# x0_logic_v0001.net
KiCad netlist of a schematic drawn in EAGLE
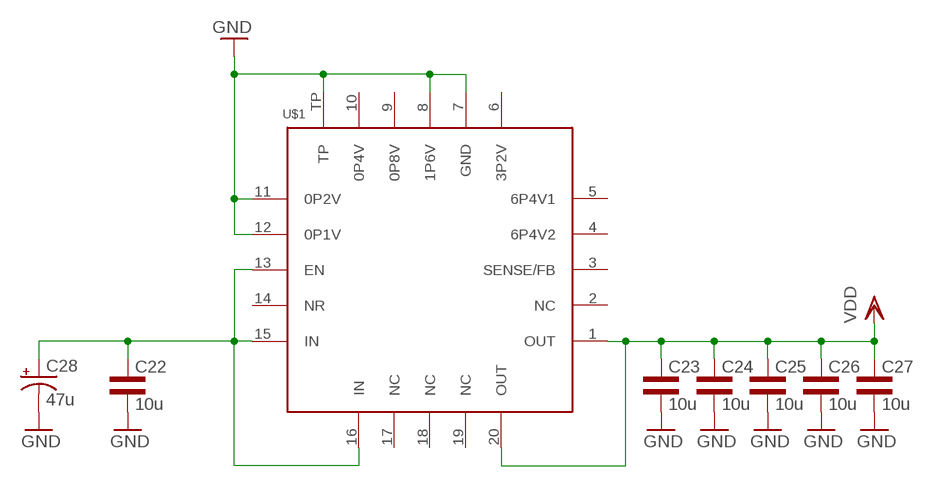
[diagram p0: schematic, sheet 1]
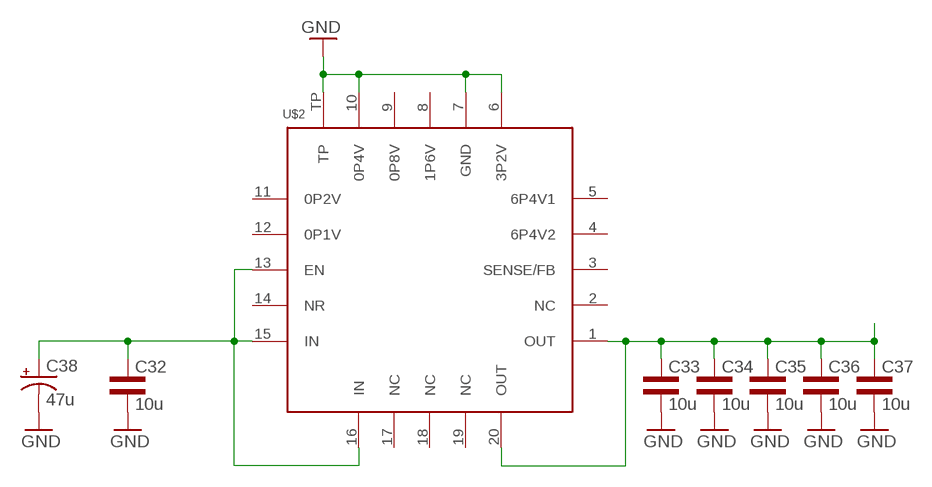
[diagram p1: schematic, sheet 2]
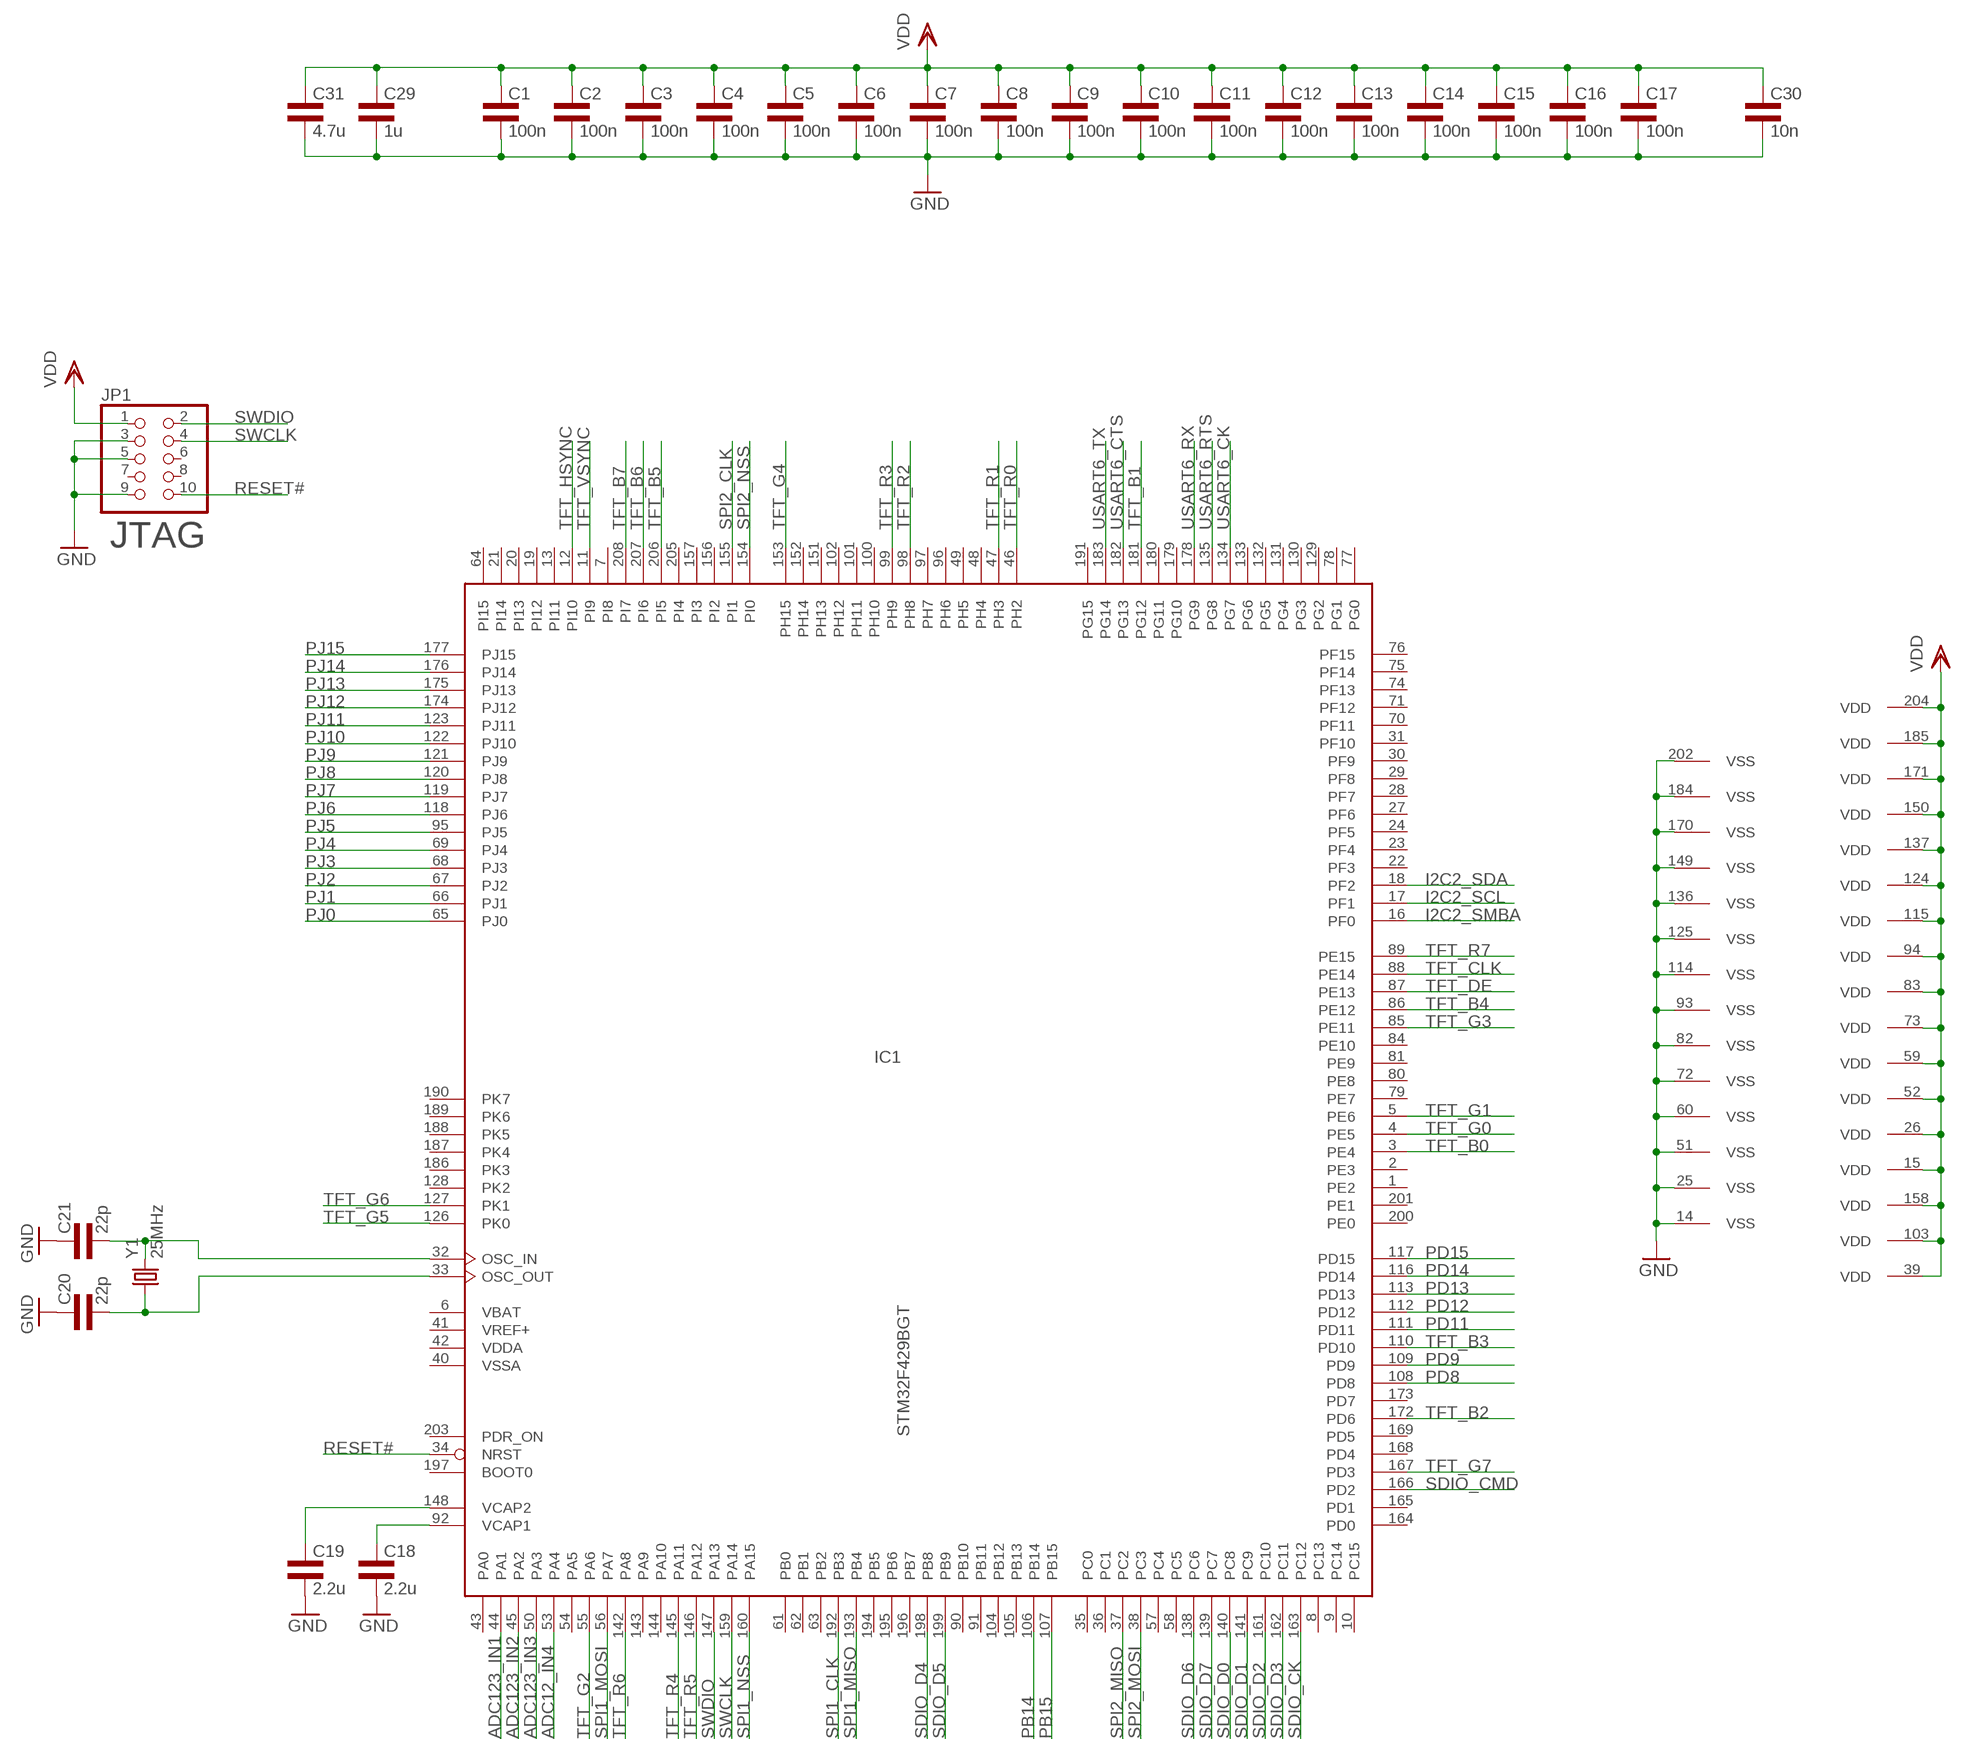
[diagram p2: schematic, sheet 3]
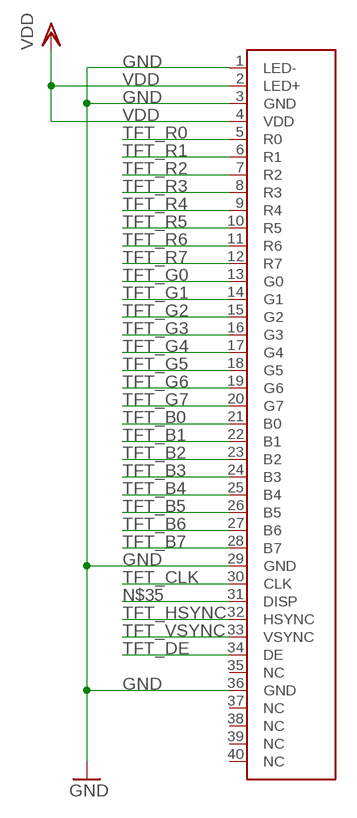
[diagram p3: schematic, sheet 4]
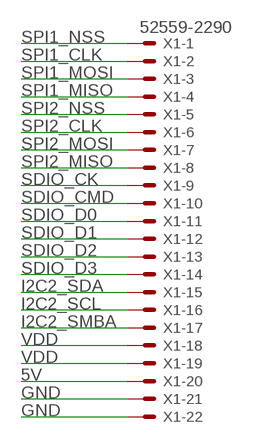
[diagram p4: schematic, sheet 5]
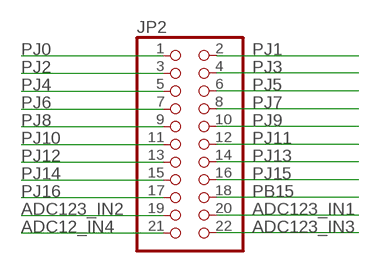
[diagram p5: schematic, sheet 6]
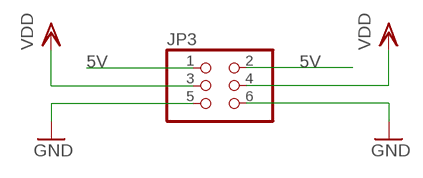
[diagram p6: schematic, sheet 7]

(export (version "E")
  (design (tool "Eeschema 10.0.6"))
  (components
    (comp (ref "C32")
      (value "10u")
      (footprint "eagle-import:1206L3")
      (libsource (lib "eagle-import") (part "CAP1206L3"))
    )
    (comp (ref "C33")
      (value "10u")
      (footprint "eagle-import:1206L3")
      (libsource (lib "eagle-import") (part "CAP1206L3"))
    )
    (comp (ref "C34")
      (value "10u")
      (footprint "eagle-import:1206L3")
      (libsource (lib "eagle-import") (part "CAP1206L3"))
    )
    (comp (ref "C35")
      (value "10u")
      (footprint "eagle-import:1206L3")
      (libsource (lib "eagle-import") (part "CAP1206L3"))
    )
    (comp (ref "C36")
      (value "10u")
      (footprint "eagle-import:1206L3")
      (libsource (lib "eagle-import") (part "CAP1206L3"))
    )
    (comp (ref "C37")
      (value "10u")
      (footprint "eagle-import:1206L3")
      (libsource (lib "eagle-import") (part "CAP1206L3"))
    )
    (comp (ref "C38")
      (value "47u")
      (footprint "eagle-import:CT7343")
      (libsource (lib "eagle-import") (part "CPOL-USCT7343"))
    )
    (comp (ref "U$2")
      (value "POWER-SUPPLY_POS_V1_TI_LDO_TPS7A4700")
      (footprint "eagle-import:POWER-SUPPLY_POS_V1_TI_LDO_VQFN-20")
      (libsource (lib "eagle-import") (part "POWER-SUPPLY_POS_V1_TI_LDO_TPS7A4700"))
    )
    (comp (ref "X1")
      (value "52559-2290")
      (footprint "eagle-import:52559-2290")
      (libsource (lib "eagle-import") (part "52559-2290"))
    )
    (comp (ref "JP3")
      (value "PINHD-2X3")
      (footprint "eagle-import:2X03")
      (libsource (lib "eagle-import") (part "PINHD-2X3"))
    )
    (comp (ref "CON1")
      (value "NH-4.3")
      (footprint "eagle-import:FPC-40")
      (libsource (lib "eagle-import") (part "NH-4.3"))
    )
    (comp (ref "C22")
      (value "10u")
      (footprint "eagle-import:1206L3")
      (libsource (lib "eagle-import") (part "CAP1206L3"))
    )
    (comp (ref "C23")
      (value "10u")
      (footprint "eagle-import:1206L3")
      (libsource (lib "eagle-import") (part "CAP1206L3"))
    )
    (comp (ref "C24")
      (value "10u")
      (footprint "eagle-import:1206L3")
      (libsource (lib "eagle-import") (part "CAP1206L3"))
    )
    (comp (ref "C25")
      (value "10u")
      (footprint "eagle-import:1206L3")
      (libsource (lib "eagle-import") (part "CAP1206L3"))
    )
    (comp (ref "C26")
      (value "10u")
      (footprint "eagle-import:1206L3")
      (libsource (lib "eagle-import") (part "CAP1206L3"))
    )
    (comp (ref "C27")
      (value "10u")
      (footprint "eagle-import:1206L3")
      (libsource (lib "eagle-import") (part "CAP1206L3"))
    )
    (comp (ref "C28")
      (value "47u")
      (footprint "eagle-import:CT7343")
      (libsource (lib "eagle-import") (part "CPOL-USCT7343"))
    )
    (comp (ref "U$1")
      (value "POWER-SUPPLY_POS_V1_TI_LDO_TPS7A4700")
      (footprint "eagle-import:POWER-SUPPLY_POS_V1_TI_LDO_VQFN-20")
      (libsource (lib "eagle-import") (part "POWER-SUPPLY_POS_V1_TI_LDO_TPS7A4700"))
    )
    (comp (ref "C1")
      (value "100n")
      (footprint "eagle-import:0402L3")
      (libsource (lib "eagle-import") (part "CAP0402L3"))
    )
    (comp (ref "C2")
      (value "100n")
      (footprint "eagle-import:0402L3")
      (libsource (lib "eagle-import") (part "CAP0402L3"))
    )
    (comp (ref "C3")
      (value "100n")
      (footprint "eagle-import:0402L3")
      (libsource (lib "eagle-import") (part "CAP0402L3"))
    )
    (comp (ref "C4")
      (value "100n")
      (footprint "eagle-import:0402L3")
      (libsource (lib "eagle-import") (part "CAP0402L3"))
    )
    (comp (ref "C5")
      (value "100n")
      (footprint "eagle-import:0402L3")
      (libsource (lib "eagle-import") (part "CAP0402L3"))
    )
    (comp (ref "C6")
      (value "100n")
      (footprint "eagle-import:0402L3")
      (libsource (lib "eagle-import") (part "CAP0402L3"))
    )
    (comp (ref "C7")
      (value "100n")
      (footprint "eagle-import:0402L3")
      (libsource (lib "eagle-import") (part "CAP0402L3"))
    )
    (comp (ref "C8")
      (value "100n")
      (footprint "eagle-import:0402L3")
      (libsource (lib "eagle-import") (part "CAP0402L3"))
    )
    (comp (ref "C9")
      (value "100n")
      (footprint "eagle-import:0402L3")
      (libsource (lib "eagle-import") (part "CAP0402L3"))
    )
    (comp (ref "C10")
      (value "100n")
      (footprint "eagle-import:0402L3")
      (libsource (lib "eagle-import") (part "CAP0402L3"))
    )
    (comp (ref "C11")
      (value "100n")
      (footprint "eagle-import:0402L3")
      (libsource (lib "eagle-import") (part "CAP0402L3"))
    )
    (comp (ref "C12")
      (value "100n")
      (footprint "eagle-import:0402L3")
      (libsource (lib "eagle-import") (part "CAP0402L3"))
    )
    (comp (ref "C13")
      (value "100n")
      (footprint "eagle-import:0402L3")
      (libsource (lib "eagle-import") (part "CAP0402L3"))
    )
    (comp (ref "C14")
      (value "100n")
      (footprint "eagle-import:0402L3")
      (libsource (lib "eagle-import") (part "CAP0402L3"))
    )
    (comp (ref "C15")
      (value "100n")
      (footprint "eagle-import:0402L3")
      (libsource (lib "eagle-import") (part "CAP0402L3"))
    )
    (comp (ref "C16")
      (value "100n")
      (footprint "eagle-import:0402L3")
      (libsource (lib "eagle-import") (part "CAP0402L3"))
    )
    (comp (ref "C17")
      (value "100n")
      (footprint "eagle-import:0402L3")
      (libsource (lib "eagle-import") (part "CAP0402L3"))
    )
    (comp (ref "C18")
      (value "2.2u")
      (footprint "eagle-import:0603L3")
      (libsource (lib "eagle-import") (part "CAP0603L3"))
    )
    (comp (ref "C19")
      (value "2.2u")
      (footprint "eagle-import:0603L3")
      (libsource (lib "eagle-import") (part "CAP0603L3"))
    )
    (comp (ref "C20")
      (value "22p")
      (footprint "eagle-import:0402L3")
      (libsource (lib "eagle-import") (part "CAP0402L3"))
    )
    (comp (ref "C21")
      (value "22p")
      (footprint "eagle-import:0402L3")
      (libsource (lib "eagle-import") (part "CAP0402L3"))
    )
    (comp (ref "C29")
      (value "1u")
      (footprint "eagle-import:0805L3")
      (libsource (lib "eagle-import") (part "CAP0805L3"))
    )
    (comp (ref "C30")
      (value "10n")
      (footprint "eagle-import:0603L3")
      (libsource (lib "eagle-import") (part "CAP0603L3"))
    )
    (comp (ref "C31")
      (value "4.7u")
      (footprint "eagle-import:0805L3")
      (libsource (lib "eagle-import") (part "CAP0805L3"))
    )
    (comp (ref "IC1")
      (value "STM32F429BGT")
      (footprint "eagle-import:LQFP208")
      (libsource (lib "eagle-import") (part "STM32F429BTG"))
    )
    (comp (ref "JP1")
      (value "PINHD-2X5")
      (footprint "eagle-import:2X05")
      (libsource (lib "eagle-import") (part "PINHD-2X5"))
    )
    (comp (ref "Y1")
      (value "25MHz")
      (footprint "eagle-import:HC49US")
      (libsource (lib "eagle-import") (part "CRYSTALHC49US"))
    )
    (comp (ref "JP2")
      (value "PINHD-2X11")
      (footprint "eagle-import:2X11")
      (libsource (lib "eagle-import") (part "PINHD-2X11"))
    )
  )
  (nets
    (net (code "1") (name "5V") (class "Default")
      (node (ref "C33") (pin "1") (pinfunction "1_1") (pintype "bidirectional"))
      (node (ref "C34") (pin "1") (pinfunction "1_1") (pintype "bidirectional"))
      (node (ref "C35") (pin "1") (pinfunction "1_1") (pintype "bidirectional"))
      (node (ref "C36") (pin "1") (pinfunction "1_1") (pintype "bidirectional"))
      (node (ref "C37") (pin "1") (pinfunction "1_1") (pintype "bidirectional"))
      (node (ref "JP3") (pin "1") (pinfunction "1_1") (pintype "passive"))
      (node (ref "JP3") (pin "2") (pinfunction "2_2") (pintype "passive"))
      (node (ref "U$2") (pin "1") (pinfunction "OUT_1") (pintype "bidirectional"))
      (node (ref "U$2") (pin "20") (pinfunction "OUT_20") (pintype "bidirectional"))
      (node (ref "X1") (pin "20") (pinfunction "S_20") (pintype "passive"))
    )
    (net (code "2") (name "ADC12_IN4") (class "Default")
      (node (ref "IC1") (pin "53") (pinfunction "PA4_53") (pintype "bidirectional"))
      (node (ref "JP2") (pin "21") (pinfunction "21_21") (pintype "passive"))
    )
    (net (code "3") (name "ADC123_IN1") (class "Default")
      (node (ref "IC1") (pin "44") (pinfunction "PA1_44") (pintype "bidirectional"))
      (node (ref "JP2") (pin "20") (pinfunction "20_20") (pintype "passive"))
    )
    (net (code "4") (name "ADC123_IN2") (class "Default")
      (node (ref "IC1") (pin "45") (pinfunction "PA2_45") (pintype "bidirectional"))
      (node (ref "JP2") (pin "19") (pinfunction "19_19") (pintype "passive"))
    )
    (net (code "5") (name "ADC123_IN3") (class "Default")
      (node (ref "IC1") (pin "50") (pinfunction "PA3_50") (pintype "bidirectional"))
      (node (ref "JP2") (pin "22") (pinfunction "22_22") (pintype "passive"))
    )
    (net (code "6") (name "BATT+") (class "Default")
      (node (ref "C22") (pin "1") (pinfunction "1_1") (pintype "bidirectional"))
      (node (ref "C28") (pin "+") (pinfunction "+_+") (pintype "passive"))
      (node (ref "C32") (pin "1") (pinfunction "1_1") (pintype "bidirectional"))
      (node (ref "C38") (pin "+") (pinfunction "+_+") (pintype "passive"))
      (node (ref "U$1") (pin "13") (pinfunction "EN_13") (pintype "bidirectional"))
      (node (ref "U$1") (pin "15") (pinfunction "IN_15") (pintype "bidirectional"))
      (node (ref "U$1") (pin "16") (pinfunction "IN_16") (pintype "bidirectional"))
      (node (ref "U$2") (pin "13") (pinfunction "EN_13") (pintype "bidirectional"))
      (node (ref "U$2") (pin "15") (pinfunction "IN_15") (pintype "bidirectional"))
      (node (ref "U$2") (pin "16") (pinfunction "IN_16") (pintype "bidirectional"))
    )
    (net (code "7") (name "GND") (class "Default")
      (node (ref "C1") (pin "P$2") (pinfunction "2_P$2") (pintype "bidirectional"))
      (node (ref "C10") (pin "P$2") (pinfunction "2_P$2") (pintype "bidirectional"))
      (node (ref "C11") (pin "P$2") (pinfunction "2_P$2") (pintype "bidirectional"))
      (node (ref "C12") (pin "P$2") (pinfunction "2_P$2") (pintype "bidirectional"))
      (node (ref "C13") (pin "P$2") (pinfunction "2_P$2") (pintype "bidirectional"))
      (node (ref "C14") (pin "P$2") (pinfunction "2_P$2") (pintype "bidirectional"))
      (node (ref "C15") (pin "P$2") (pinfunction "2_P$2") (pintype "bidirectional"))
      (node (ref "C16") (pin "P$2") (pinfunction "2_P$2") (pintype "bidirectional"))
      (node (ref "C17") (pin "P$2") (pinfunction "2_P$2") (pintype "bidirectional"))
      (node (ref "C18") (pin "P$2") (pinfunction "2_P$2") (pintype "bidirectional"))
      (node (ref "C19") (pin "P$2") (pinfunction "2_P$2") (pintype "bidirectional"))
      (node (ref "C2") (pin "P$2") (pinfunction "2_P$2") (pintype "bidirectional"))
      (node (ref "C20") (pin "P$1") (pinfunction "1_P$1") (pintype "bidirectional"))
      (node (ref "C21") (pin "P$1") (pinfunction "1_P$1") (pintype "bidirectional"))
      (node (ref "C22") (pin "2") (pinfunction "2_2") (pintype "bidirectional"))
      (node (ref "C23") (pin "2") (pinfunction "2_2") (pintype "bidirectional"))
      (node (ref "C24") (pin "2") (pinfunction "2_2") (pintype "bidirectional"))
      (node (ref "C25") (pin "2") (pinfunction "2_2") (pintype "bidirectional"))
      (node (ref "C26") (pin "2") (pinfunction "2_2") (pintype "bidirectional"))
      (node (ref "C27") (pin "2") (pinfunction "2_2") (pintype "bidirectional"))
      (node (ref "C28") (pin "-") (pinfunction "-_-") (pintype "passive"))
      (node (ref "C29") (pin "2") (pinfunction "2_2") (pintype "bidirectional"))
      (node (ref "C3") (pin "P$2") (pinfunction "2_P$2") (pintype "bidirectional"))
      (node (ref "C30") (pin "P$2") (pinfunction "2_P$2") (pintype "bidirectional"))
      (node (ref "C31") (pin "2") (pinfunction "2_2") (pintype "bidirectional"))
      (node (ref "C32") (pin "2") (pinfunction "2_2") (pintype "bidirectional"))
      (node (ref "C33") (pin "2") (pinfunction "2_2") (pintype "bidirectional"))
      (node (ref "C34") (pin "2") (pinfunction "2_2") (pintype "bidirectional"))
      (node (ref "C35") (pin "2") (pinfunction "2_2") (pintype "bidirectional"))
      (node (ref "C36") (pin "2") (pinfunction "2_2") (pintype "bidirectional"))
      (node (ref "C37") (pin "2") (pinfunction "2_2") (pintype "bidirectional"))
      (node (ref "C38") (pin "-") (pinfunction "-_-") (pintype "passive"))
      (node (ref "C4") (pin "P$2") (pinfunction "2_P$2") (pintype "bidirectional"))
      (node (ref "C5") (pin "P$2") (pinfunction "2_P$2") (pintype "bidirectional"))
      (node (ref "C6") (pin "P$2") (pinfunction "2_P$2") (pintype "bidirectional"))
      (node (ref "C7") (pin "P$2") (pinfunction "2_P$2") (pintype "bidirectional"))
      (node (ref "C8") (pin "P$2") (pinfunction "2_P$2") (pintype "bidirectional"))
      (node (ref "C9") (pin "P$2") (pinfunction "2_P$2") (pintype "bidirectional"))
      (node (ref "CON1") (pin "1") (pinfunction "LED-_1") (pintype "bidirectional"))
      (node (ref "CON1") (pin "29") (pinfunction "GND_29") (pintype "bidirectional"))
      (node (ref "CON1") (pin "3") (pinfunction "GND_3") (pintype "bidirectional"))
      (node (ref "CON1") (pin "36") (pinfunction "GND_36") (pintype "bidirectional"))
      (node (ref "IC1") (pin "114") (pinfunction "VSS_114") (pintype "power_in"))
      (node (ref "IC1") (pin "125") (pinfunction "VSS_125") (pintype "power_in"))
      (node (ref "IC1") (pin "136") (pinfunction "VSS_136") (pintype "power_in"))
      (node (ref "IC1") (pin "14") (pinfunction "VSS_14") (pintype "power_in"))
      (node (ref "IC1") (pin "149") (pinfunction "VSS_149") (pintype "power_in"))
      (node (ref "IC1") (pin "170") (pinfunction "VSS_170") (pintype "power_in"))
      (node (ref "IC1") (pin "184") (pinfunction "VSS_184") (pintype "power_in"))
      (node (ref "IC1") (pin "202") (pinfunction "VSS_202") (pintype "power_in"))
      (node (ref "IC1") (pin "25") (pinfunction "VSS_25") (pintype "power_in"))
      (node (ref "IC1") (pin "51") (pinfunction "VSS_51") (pintype "power_in"))
      (node (ref "IC1") (pin "60") (pinfunction "VSS_60") (pintype "power_in"))
      (node (ref "IC1") (pin "72") (pinfunction "VSS_72") (pintype "power_in"))
      (node (ref "IC1") (pin "82") (pinfunction "VSS_82") (pintype "power_in"))
      (node (ref "IC1") (pin "93") (pinfunction "VSS_93") (pintype "power_in"))
      (node (ref "JP1") (pin "3") (pinfunction "3_3") (pintype "passive"))
      (node (ref "JP1") (pin "5") (pinfunction "5_5") (pintype "passive"))
      (node (ref "JP1") (pin "9") (pinfunction "9_9") (pintype "passive"))
      (node (ref "JP3") (pin "5") (pinfunction "5_5") (pintype "passive"))
      (node (ref "JP3") (pin "6") (pinfunction "6_6") (pintype "passive"))
      (node (ref "U$1") (pin "11") (pinfunction "0P2V_11") (pintype "bidirectional"))
      (node (ref "U$1") (pin "12") (pinfunction "0P1V_12") (pintype "bidirectional"))
      (node (ref "U$1") (pin "7") (pinfunction "GND_7") (pintype "bidirectional"))
      (node (ref "U$1") (pin "8") (pinfunction "1P6V_8") (pintype "bidirectional"))
      (node (ref "U$1") (pin "TP") (pinfunction "TP_TP") (pintype "bidirectional"))
      (node (ref "U$2") (pin "10") (pinfunction "0P4V_10") (pintype "bidirectional"))
      (node (ref "U$2") (pin "6") (pinfunction "3P2V_6") (pintype "bidirectional"))
      (node (ref "U$2") (pin "7") (pinfunction "GND_7") (pintype "bidirectional"))
      (node (ref "U$2") (pin "TP") (pinfunction "TP_TP") (pintype "bidirectional"))
      (node (ref "X1") (pin "21") (pinfunction "S_21") (pintype "passive"))
      (node (ref "X1") (pin "22") (pinfunction "S_22") (pintype "passive"))
    )
    (net (code "8") (name "I2C2_SCL") (class "Default")
      (node (ref "IC1") (pin "17") (pinfunction "PF1_17") (pintype "bidirectional"))
      (node (ref "X1") (pin "16") (pinfunction "S_16") (pintype "passive"))
    )
    (net (code "9") (name "I2C2_SDA") (class "Default")
      (node (ref "IC1") (pin "18") (pinfunction "PF2_18") (pintype "bidirectional"))
      (node (ref "X1") (pin "15") (pinfunction "S_15") (pintype "passive"))
    )
    (net (code "10") (name "I2C2_SMBA") (class "Default")
      (node (ref "IC1") (pin "16") (pinfunction "PF0_16") (pintype "bidirectional"))
      (node (ref "X1") (pin "17") (pinfunction "S_17") (pintype "passive"))
    )
    (net (code "11") (name "N$35") (class "Default")
      (node (ref "CON1") (pin "31") (pinfunction "DISP_31") (pintype "bidirectional"))
    )
    (net (code "12") (name "Net-(C18-1)") (class "Default")
      (node (ref "C18") (pin "P$1") (pinfunction "1_P$1") (pintype "bidirectional"))
      (node (ref "IC1") (pin "92") (pinfunction "VCAP1_92") (pintype "power_in"))
    )
    (net (code "13") (name "Net-(C19-1)") (class "Default")
      (node (ref "C19") (pin "P$1") (pinfunction "1_P$1") (pintype "bidirectional"))
      (node (ref "IC1") (pin "148") (pinfunction "VCAP2_148") (pintype "power_in"))
    )
    (net (code "14") (name "Net-(C20-2)") (class "Default")
      (node (ref "C20") (pin "P$2") (pinfunction "2_P$2") (pintype "bidirectional"))
      (node (ref "IC1") (pin "33") (pinfunction "OSC_OUT_33") (pintype "bidirectional"))
      (node (ref "Y1") (pin "1") (pinfunction "1_1") (pintype "passive"))
    )
    (net (code "15") (name "Net-(C21-2)") (class "Default")
      (node (ref "C21") (pin "P$2") (pinfunction "2_P$2") (pintype "bidirectional"))
      (node (ref "IC1") (pin "32") (pinfunction "OSC_IN_32") (pintype "bidirectional"))
      (node (ref "Y1") (pin "2") (pinfunction "2_2") (pintype "passive"))
    )
    (net (code "16") (name "PB14") (class "Default")
      (node (ref "IC1") (pin "106") (pinfunction "PB14_106") (pintype "bidirectional"))
    )
    (net (code "17") (name "PB15") (class "Default")
      (node (ref "IC1") (pin "107") (pinfunction "PB15_107") (pintype "bidirectional"))
      (node (ref "JP2") (pin "18") (pinfunction "18_18") (pintype "passive"))
    )
    (net (code "18") (name "PD8") (class "Default")
      (node (ref "IC1") (pin "108") (pinfunction "PD8_108") (pintype "bidirectional"))
    )
    (net (code "19") (name "PD9") (class "Default")
      (node (ref "IC1") (pin "109") (pinfunction "PD9_109") (pintype "bidirectional"))
    )
    (net (code "20") (name "PD11") (class "Default")
      (node (ref "IC1") (pin "111") (pinfunction "PD11_111") (pintype "bidirectional"))
    )
    (net (code "21") (name "PD12") (class "Default")
      (node (ref "IC1") (pin "112") (pinfunction "PD12_112") (pintype "bidirectional"))
    )
    (net (code "22") (name "PD13") (class "Default")
      (node (ref "IC1") (pin "113") (pinfunction "PD13_113") (pintype "bidirectional"))
    )
    (net (code "23") (name "PD14") (class "Default")
      (node (ref "IC1") (pin "116") (pinfunction "PD14_116") (pintype "bidirectional"))
    )
    (net (code "24") (name "PD15") (class "Default")
      (node (ref "IC1") (pin "117") (pinfunction "PD15_117") (pintype "bidirectional"))
    )
    (net (code "25") (name "PJ0") (class "Default")
      (node (ref "IC1") (pin "65") (pinfunction "PJ0_65") (pintype "bidirectional"))
      (node (ref "JP2") (pin "1") (pinfunction "1_1") (pintype "passive"))
    )
    (net (code "26") (name "PJ1") (class "Default")
      (node (ref "IC1") (pin "66") (pinfunction "PJ1_66") (pintype "bidirectional"))
      (node (ref "JP2") (pin "2") (pinfunction "2_2") (pintype "passive"))
    )
    (net (code "27") (name "PJ2") (class "Default")
      (node (ref "IC1") (pin "67") (pinfunction "PJ2_67") (pintype "bidirectional"))
      (node (ref "JP2") (pin "3") (pinfunction "3_3") (pintype "passive"))
    )
    (net (code "28") (name "PJ3") (class "Default")
      (node (ref "IC1") (pin "68") (pinfunction "PJ3_68") (pintype "bidirectional"))
      (node (ref "JP2") (pin "4") (pinfunction "4_4") (pintype "passive"))
    )
    (net (code "29") (name "PJ4") (class "Default")
      (node (ref "IC1") (pin "69") (pinfunction "PJ4_69") (pintype "bidirectional"))
      (node (ref "JP2") (pin "5") (pinfunction "5_5") (pintype "passive"))
    )
    (net (code "30") (name "PJ5") (class "Default")
      (node (ref "IC1") (pin "95") (pinfunction "PJ5_95") (pintype "bidirectional"))
      (node (ref "JP2") (pin "6") (pinfunction "6_6") (pintype "passive"))
    )
    (net (code "31") (name "PJ6") (class "Default")
      (node (ref "IC1") (pin "118") (pinfunction "PJ6_118") (pintype "bidirectional"))
      (node (ref "JP2") (pin "7") (pinfunction "7_7") (pintype "passive"))
    )
    (net (code "32") (name "PJ7") (class "Default")
      (node (ref "IC1") (pin "119") (pinfunction "PJ7_119") (pintype "bidirectional"))
      (node (ref "JP2") (pin "8") (pinfunction "8_8") (pintype "passive"))
    )
    (net (code "33") (name "PJ8") (class "Default")
      (node (ref "IC1") (pin "120") (pinfunction "PJ8_120") (pintype "bidirectional"))
      (node (ref "JP2") (pin "9") (pinfunction "9_9") (pintype "passive"))
    )
    (net (code "34") (name "PJ9") (class "Default")
      (node (ref "IC1") (pin "121") (pinfunction "PJ9_121") (pintype "bidirectional"))
      (node (ref "JP2") (pin "10") (pinfunction "10_10") (pintype "passive"))
    )
    (net (code "35") (name "PJ10") (class "Default")
      (node (ref "IC1") (pin "122") (pinfunction "PJ10_122") (pintype "bidirectional"))
      (node (ref "JP2") (pin "11") (pinfunction "11_11") (pintype "passive"))
    )
    (net (code "36") (name "PJ11") (class "Default")
      (node (ref "IC1") (pin "123") (pinfunction "PJ11_123") (pintype "bidirectional"))
      (node (ref "JP2") (pin "12") (pinfunction "12_12") (pintype "passive"))
    )
    (net (code "37") (name "PJ12") (class "Default")
      (node (ref "IC1") (pin "174") (pinfunction "PJ12_174") (pintype "bidirectional"))
      (node (ref "JP2") (pin "13") (pinfunction "13_13") (pintype "passive"))
    )
    (net (code "38") (name "PJ13") (class "Default")
      (node (ref "IC1") (pin "175") (pinfunction "PJ13_175") (pintype "bidirectional"))
      (node (ref "JP2") (pin "14") (pinfunction "14_14") (pintype "passive"))
    )
    (net (code "39") (name "PJ14") (class "Default")
      (node (ref "IC1") (pin "176") (pinfunction "PJ14_176") (pintype "bidirectional"))
      (node (ref "JP2") (pin "15") (pinfunction "15_15") (pintype "passive"))
    )
    (net (code "40") (name "PJ15") (class "Default")
      (node (ref "IC1") (pin "177") (pinfunction "PJ15_177") (pintype "bidirectional"))
      (node (ref "JP2") (pin "16") (pinfunction "16_16") (pintype "passive"))
    )
    (net (code "41") (name "PJ16") (class "Default")
      (node (ref "JP2") (pin "17") (pinfunction "17_17") (pintype "passive"))
    )
    (net (code "42") (name "RESET#") (class "Default")
      (node (ref "IC1") (pin "34") (pinfunction "NRST_34") (pintype "bidirectional"))
      (node (ref "JP1") (pin "10") (pinfunction "10_10") (pintype "passive"))
    )
    (net (code "43") (name "SDIO_CK") (class "Default")
      (node (ref "IC1") (pin "163") (pinfunction "PC12_163") (pintype "bidirectional"))
      (node (ref "X1") (pin "9") (pinfunction "S_9") (pintype "passive"))
    )
    (net (code "44") (name "SDIO_CMD") (class "Default")
      (node (ref "IC1") (pin "166") (pinfunction "PD2_166") (pintype "bidirectional"))
      (node (ref "X1") (pin "10") (pinfunction "S_10") (pintype "passive"))
    )
    (net (code "45") (name "SDIO_D0") (class "Default")
      (node (ref "IC1") (pin "140") (pinfunction "PC8_140") (pintype "bidirectional"))
      (node (ref "X1") (pin "11") (pinfunction "S_11") (pintype "passive"))
    )
    (net (code "46") (name "SDIO_D1") (class "Default")
      (node (ref "IC1") (pin "141") (pinfunction "PC9_141") (pintype "bidirectional"))
      (node (ref "X1") (pin "12") (pinfunction "S_12") (pintype "passive"))
    )
    (net (code "47") (name "SDIO_D2") (class "Default")
      (node (ref "IC1") (pin "161") (pinfunction "PC10_161") (pintype "bidirectional"))
      (node (ref "X1") (pin "13") (pinfunction "S_13") (pintype "passive"))
    )
    (net (code "48") (name "SDIO_D3") (class "Default")
      (node (ref "IC1") (pin "162") (pinfunction "PC11_162") (pintype "bidirectional"))
      (node (ref "X1") (pin "14") (pinfunction "S_14") (pintype "passive"))
    )
    (net (code "49") (name "SDIO_D4") (class "Default")
      (node (ref "IC1") (pin "198") (pinfunction "PB8_198") (pintype "bidirectional"))
    )
    (net (code "50") (name "SDIO_D5") (class "Default")
      (node (ref "IC1") (pin "199") (pinfunction "PB9_199") (pintype "bidirectional"))
    )
    (net (code "51") (name "SDIO_D6") (class "Default")
      (node (ref "IC1") (pin "138") (pinfunction "PC6_138") (pintype "bidirectional"))
    )
    (net (code "52") (name "SDIO_D7") (class "Default")
      (node (ref "IC1") (pin "139") (pinfunction "PC7_139") (pintype "bidirectional"))
    )
    (net (code "53") (name "SPI1_CLK") (class "Default")
      (node (ref "IC1") (pin "192") (pinfunction "PB3_192") (pintype "bidirectional"))
      (node (ref "X1") (pin "2") (pinfunction "S_2") (pintype "passive"))
    )
    (net (code "54") (name "SPI1_MISO") (class "Default")
      (node (ref "IC1") (pin "193") (pinfunction "PB4_193") (pintype "bidirectional"))
      (node (ref "X1") (pin "4") (pinfunction "S_4") (pintype "passive"))
    )
    (net (code "55") (name "SPI1_MOSI") (class "Default")
      (node (ref "IC1") (pin "56") (pinfunction "PA7_56") (pintype "bidirectional"))
      (node (ref "X1") (pin "3") (pinfunction "S_3") (pintype "passive"))
    )
    (net (code "56") (name "SPI1_NSS") (class "Default")
      (node (ref "IC1") (pin "160") (pinfunction "PA15_160") (pintype "bidirectional"))
      (node (ref "X1") (pin "1") (pinfunction "S_1") (pintype "passive"))
    )
    (net (code "57") (name "SPI2_CLK") (class "Default")
      (node (ref "IC1") (pin "155") (pinfunction "PI1_155") (pintype "bidirectional"))
      (node (ref "X1") (pin "6") (pinfunction "S_6") (pintype "passive"))
    )
    (net (code "58") (name "SPI2_MISO") (class "Default")
      (node (ref "IC1") (pin "37") (pinfunction "PC2_37") (pintype "bidirectional"))
      (node (ref "X1") (pin "8") (pinfunction "S_8") (pintype "passive"))
    )
    (net (code "59") (name "SPI2_MOSI") (class "Default")
      (node (ref "IC1") (pin "38") (pinfunction "PC3_38") (pintype "bidirectional"))
      (node (ref "X1") (pin "7") (pinfunction "S_7") (pintype "passive"))
    )
    (net (code "60") (name "SPI2_NSS") (class "Default")
      (node (ref "IC1") (pin "154") (pinfunction "PI0_154") (pintype "bidirectional"))
      (node (ref "X1") (pin "5") (pinfunction "S_5") (pintype "passive"))
    )
    (net (code "61") (name "SWCLK") (class "Default")
      (node (ref "IC1") (pin "159") (pinfunction "PA14_159") (pintype "bidirectional"))
      (node (ref "JP1") (pin "4") (pinfunction "4_4") (pintype "passive"))
    )
    (net (code "62") (name "SWDIO") (class "Default")
      (node (ref "IC1") (pin "147") (pinfunction "PA13_147") (pintype "bidirectional"))
      (node (ref "JP1") (pin "2") (pinfunction "2_2") (pintype "passive"))
    )
    (net (code "63") (name "TFT_B0") (class "Default")
      (node (ref "CON1") (pin "21") (pinfunction "B0_21") (pintype "bidirectional"))
      (node (ref "IC1") (pin "3") (pinfunction "PE4_3") (pintype "bidirectional"))
    )
    (net (code "64") (name "TFT_B1") (class "Default")
      (node (ref "CON1") (pin "22") (pinfunction "B1_22") (pintype "bidirectional"))
      (node (ref "IC1") (pin "181") (pinfunction "PG12_181") (pintype "bidirectional"))
    )
    (net (code "65") (name "TFT_B2") (class "Default")
      (node (ref "CON1") (pin "23") (pinfunction "B2_23") (pintype "bidirectional"))
      (node (ref "IC1") (pin "172") (pinfunction "PD6_172") (pintype "bidirectional"))
    )
    (net (code "66") (name "TFT_B3") (class "Default")
      (node (ref "CON1") (pin "24") (pinfunction "B3_24") (pintype "bidirectional"))
      (node (ref "IC1") (pin "110") (pinfunction "PD10_110") (pintype "bidirectional"))
    )
    (net (code "67") (name "TFT_B4") (class "Default")
      (node (ref "CON1") (pin "25") (pinfunction "B4_25") (pintype "bidirectional"))
      (node (ref "IC1") (pin "86") (pinfunction "PE12_86") (pintype "bidirectional"))
    )
    (net (code "68") (name "TFT_B5") (class "Default")
      (node (ref "CON1") (pin "26") (pinfunction "B5_26") (pintype "bidirectional"))
      (node (ref "IC1") (pin "206") (pinfunction "PI5_206") (pintype "bidirectional"))
    )
    (net (code "69") (name "TFT_B6") (class "Default")
      (node (ref "CON1") (pin "27") (pinfunction "B6_27") (pintype "bidirectional"))
      (node (ref "IC1") (pin "207") (pinfunction "PI6_207") (pintype "bidirectional"))
    )
    (net (code "70") (name "TFT_B7") (class "Default")
      (node (ref "CON1") (pin "28") (pinfunction "B7_28") (pintype "bidirectional"))
      (node (ref "IC1") (pin "208") (pinfunction "PI7_208") (pintype "bidirectional"))
    )
    (net (code "71") (name "TFT_CLK") (class "Default")
      (node (ref "CON1") (pin "30") (pinfunction "CLK_30") (pintype "bidirectional"))
      (node (ref "IC1") (pin "88") (pinfunction "PE14_88") (pintype "bidirectional"))
    )
    (net (code "72") (name "TFT_DE") (class "Default")
      (node (ref "CON1") (pin "34") (pinfunction "DE_34") (pintype "bidirectional"))
      (node (ref "IC1") (pin "87") (pinfunction "PE13_87") (pintype "bidirectional"))
    )
    (net (code "73") (name "TFT_G0") (class "Default")
      (node (ref "CON1") (pin "13") (pinfunction "G0_13") (pintype "bidirectional"))
      (node (ref "IC1") (pin "4") (pinfunction "PE5_4") (pintype "bidirectional"))
    )
    (net (code "74") (name "TFT_G1") (class "Default")
      (node (ref "CON1") (pin "14") (pinfunction "G1_14") (pintype "bidirectional"))
      (node (ref "IC1") (pin "5") (pinfunction "PE6_5") (pintype "bidirectional"))
    )
    (net (code "75") (name "TFT_G2") (class "Default")
      (node (ref "CON1") (pin "15") (pinfunction "G2_15") (pintype "bidirectional"))
      (node (ref "IC1") (pin "55") (pinfunction "PA6_55") (pintype "bidirectional"))
    )
    (net (code "76") (name "TFT_G3") (class "Default")
      (node (ref "CON1") (pin "16") (pinfunction "G3_16") (pintype "bidirectional"))
      (node (ref "IC1") (pin "85") (pinfunction "PE11_85") (pintype "bidirectional"))
    )
    (net (code "77") (name "TFT_G4") (class "Default")
      (node (ref "CON1") (pin "17") (pinfunction "G4_17") (pintype "bidirectional"))
      (node (ref "IC1") (pin "153") (pinfunction "PH15_153") (pintype "bidirectional"))
    )
    (net (code "78") (name "TFT_G5") (class "Default")
      (node (ref "CON1") (pin "18") (pinfunction "G5_18") (pintype "bidirectional"))
      (node (ref "IC1") (pin "126") (pinfunction "PK0_126") (pintype "bidirectional"))
    )
    (net (code "79") (name "TFT_G6") (class "Default")
      (node (ref "CON1") (pin "19") (pinfunction "G6_19") (pintype "bidirectional"))
      (node (ref "IC1") (pin "127") (pinfunction "PK1_127") (pintype "bidirectional"))
    )
    (net (code "80") (name "TFT_G7") (class "Default")
      (node (ref "CON1") (pin "20") (pinfunction "G7_20") (pintype "bidirectional"))
      (node (ref "IC1") (pin "167") (pinfunction "PD3_167") (pintype "bidirectional"))
    )
    (net (code "81") (name "TFT_HSYNC") (class "Default")
      (node (ref "CON1") (pin "32") (pinfunction "HSYNC_32") (pintype "bidirectional"))
      (node (ref "IC1") (pin "12") (pinfunction "PI10_12") (pintype "bidirectional"))
    )
    (net (code "82") (name "TFT_R0") (class "Default")
      (node (ref "CON1") (pin "5") (pinfunction "R0_5") (pintype "bidirectional"))
      (node (ref "IC1") (pin "46") (pinfunction "PH2_46") (pintype "bidirectional"))
    )
    (net (code "83") (name "TFT_R1") (class "Default")
      (node (ref "CON1") (pin "6") (pinfunction "R1_6") (pintype "bidirectional"))
      (node (ref "IC1") (pin "47") (pinfunction "PH3_47") (pintype "bidirectional"))
    )
    (net (code "84") (name "TFT_R2") (class "Default")
      (node (ref "CON1") (pin "7") (pinfunction "R2_7") (pintype "bidirectional"))
      (node (ref "IC1") (pin "98") (pinfunction "PH8_98") (pintype "bidirectional"))
    )
    (net (code "85") (name "TFT_R3") (class "Default")
      (node (ref "CON1") (pin "8") (pinfunction "R3_8") (pintype "bidirectional"))
      (node (ref "IC1") (pin "99") (pinfunction "PH9_99") (pintype "bidirectional"))
    )
    (net (code "86") (name "TFT_R4") (class "Default")
      (node (ref "CON1") (pin "9") (pinfunction "R4_9") (pintype "bidirectional"))
      (node (ref "IC1") (pin "145") (pinfunction "PA11_145") (pintype "bidirectional"))
    )
    (net (code "87") (name "TFT_R5") (class "Default")
      (node (ref "CON1") (pin "10") (pinfunction "R5_10") (pintype "bidirectional"))
      (node (ref "IC1") (pin "146") (pinfunction "PA12_146") (pintype "bidirectional"))
    )
    (net (code "88") (name "TFT_R6") (class "Default")
      (node (ref "CON1") (pin "11") (pinfunction "R6_11") (pintype "bidirectional"))
      (node (ref "IC1") (pin "142") (pinfunction "PA8_142") (pintype "bidirectional"))
    )
    (net (code "89") (name "TFT_R7") (class "Default")
      (node (ref "CON1") (pin "12") (pinfunction "R7_12") (pintype "bidirectional"))
      (node (ref "IC1") (pin "89") (pinfunction "PE15_89") (pintype "bidirectional"))
    )
    (net (code "90") (name "TFT_VSYNC") (class "Default")
      (node (ref "CON1") (pin "33") (pinfunction "VSYNC_33") (pintype "bidirectional"))
      (node (ref "IC1") (pin "11") (pinfunction "PI9_11") (pintype "bidirectional"))
    )
    (net (code "91") (name "USART6_CK") (class "Default")
      (node (ref "IC1") (pin "134") (pinfunction "PG7_134") (pintype "bidirectional"))
    )
    (net (code "92") (name "USART6_CTS") (class "Default")
      (node (ref "IC1") (pin "182") (pinfunction "PG13_182") (pintype "bidirectional"))
    )
    (net (code "93") (name "USART6_RTS") (class "Default")
      (node (ref "IC1") (pin "135") (pinfunction "PG8_135") (pintype "bidirectional"))
    )
    (net (code "94") (name "USART6_RX") (class "Default")
      (node (ref "IC1") (pin "178") (pinfunction "PG9_178") (pintype "bidirectional"))
    )
    (net (code "95") (name "USART6_TX") (class "Default")
      (node (ref "IC1") (pin "183") (pinfunction "PG14_183") (pintype "bidirectional"))
    )
    (net (code "96") (name "VBAT") (class "Default")
      (node (ref "IC1") (pin "6") (pinfunction "VBAT_6") (pintype "power_in"))
    )
    (net (code "97") (name "VDD") (class "Default")
      (node (ref "C1") (pin "P$1") (pinfunction "1_P$1") (pintype "bidirectional"))
      (node (ref "C10") (pin "P$1") (pinfunction "1_P$1") (pintype "bidirectional"))
      (node (ref "C11") (pin "P$1") (pinfunction "1_P$1") (pintype "bidirectional"))
      (node (ref "C12") (pin "P$1") (pinfunction "1_P$1") (pintype "bidirectional"))
      (node (ref "C13") (pin "P$1") (pinfunction "1_P$1") (pintype "bidirectional"))
      (node (ref "C14") (pin "P$1") (pinfunction "1_P$1") (pintype "bidirectional"))
      (node (ref "C15") (pin "P$1") (pinfunction "1_P$1") (pintype "bidirectional"))
      (node (ref "C16") (pin "P$1") (pinfunction "1_P$1") (pintype "bidirectional"))
      (node (ref "C17") (pin "P$1") (pinfunction "1_P$1") (pintype "bidirectional"))
      (node (ref "C2") (pin "P$1") (pinfunction "1_P$1") (pintype "bidirectional"))
      (node (ref "C23") (pin "1") (pinfunction "1_1") (pintype "bidirectional"))
      (node (ref "C24") (pin "1") (pinfunction "1_1") (pintype "bidirectional"))
      (node (ref "C25") (pin "1") (pinfunction "1_1") (pintype "bidirectional"))
      (node (ref "C26") (pin "1") (pinfunction "1_1") (pintype "bidirectional"))
      (node (ref "C27") (pin "1") (pinfunction "1_1") (pintype "bidirectional"))
      (node (ref "C29") (pin "1") (pinfunction "1_1") (pintype "bidirectional"))
      (node (ref "C3") (pin "P$1") (pinfunction "1_P$1") (pintype "bidirectional"))
      (node (ref "C30") (pin "P$1") (pinfunction "1_P$1") (pintype "bidirectional"))
      (node (ref "C31") (pin "1") (pinfunction "1_1") (pintype "bidirectional"))
      (node (ref "C4") (pin "P$1") (pinfunction "1_P$1") (pintype "bidirectional"))
      (node (ref "C5") (pin "P$1") (pinfunction "1_P$1") (pintype "bidirectional"))
      (node (ref "C6") (pin "P$1") (pinfunction "1_P$1") (pintype "bidirectional"))
      (node (ref "C7") (pin "P$1") (pinfunction "1_P$1") (pintype "bidirectional"))
      (node (ref "C8") (pin "P$1") (pinfunction "1_P$1") (pintype "bidirectional"))
      (node (ref "C9") (pin "P$1") (pinfunction "1_P$1") (pintype "bidirectional"))
      (node (ref "CON1") (pin "2") (pinfunction "LED+_2") (pintype "bidirectional"))
      (node (ref "CON1") (pin "4") (pinfunction "VDD_4") (pintype "bidirectional"))
      (node (ref "IC1") (pin "103") (pinfunction "VDD_103") (pintype "power_in"))
      (node (ref "IC1") (pin "115") (pinfunction "VDD_115") (pintype "power_in"))
      (node (ref "IC1") (pin "124") (pinfunction "VDD_124") (pintype "power_in"))
      (node (ref "IC1") (pin "137") (pinfunction "VDD_137") (pintype "power_in"))
      (node (ref "IC1") (pin "15") (pinfunction "VDD_15") (pintype "power_in"))
      (node (ref "IC1") (pin "150") (pinfunction "VDD_150") (pintype "power_in"))
      (node (ref "IC1") (pin "158") (pinfunction "VDD_158") (pintype "power_in"))
      (node (ref "IC1") (pin "171") (pinfunction "VDD_171") (pintype "power_in"))
      (node (ref "IC1") (pin "185") (pinfunction "VDD_185") (pintype "power_in"))
      (node (ref "IC1") (pin "204") (pinfunction "VDD_204") (pintype "power_in"))
      (node (ref "IC1") (pin "26") (pinfunction "VDD_26") (pintype "power_in"))
      (node (ref "IC1") (pin "39") (pinfunction "VDD_39") (pintype "power_in"))
      (node (ref "IC1") (pin "52") (pinfunction "VDD_52") (pintype "power_in"))
      (node (ref "IC1") (pin "59") (pinfunction "VDD_59") (pintype "power_in"))
      (node (ref "IC1") (pin "73") (pinfunction "VDD_73") (pintype "power_in"))
      (node (ref "IC1") (pin "83") (pinfunction "VDD_83") (pintype "power_in"))
      (node (ref "IC1") (pin "94") (pinfunction "VDD_94") (pintype "power_in"))
      (node (ref "JP1") (pin "1") (pinfunction "1_1") (pintype "passive"))
      (node (ref "JP3") (pin "3") (pinfunction "3_3") (pintype "passive"))
      (node (ref "JP3") (pin "4") (pinfunction "4_4") (pintype "passive"))
      (node (ref "U$1") (pin "1") (pinfunction "OUT_1") (pintype "bidirectional"))
      (node (ref "U$1") (pin "20") (pinfunction "OUT_20") (pintype "bidirectional"))
      (node (ref "X1") (pin "18") (pinfunction "S_18") (pintype "passive"))
      (node (ref "X1") (pin "19") (pinfunction "S_19") (pintype "passive"))
    )
    (net (code "98") (name "VDDA") (class "Default")
      (node (ref "IC1") (pin "42") (pinfunction "VDDA_42") (pintype "power_in"))
    )
    (net (code "99") (name "VREF+") (class "Default")
      (node (ref "IC1") (pin "41") (pinfunction "VREF+_41") (pintype "power_in"))
    )
    (net (code "100") (name "VSSA") (class "Default")
      (node (ref "IC1") (pin "40") (pinfunction "VSSA_40") (pintype "power_in"))
    )
    (net (code "101") (name "unconnected-(CON1-NC-Pad35)") (class "Default")
      (node (ref "CON1") (pin "35") (pinfunction "NC_35") (pintype "bidirectional"))
    )
    (net (code "102") (name "unconnected-(CON1-NC-Pad37)") (class "Default")
      (node (ref "CON1") (pin "37") (pinfunction "NC_37") (pintype "bidirectional"))
    )
    (net (code "103") (name "unconnected-(CON1-NC-Pad38)") (class "Default")
      (node (ref "CON1") (pin "38") (pinfunction "NC_38") (pintype "bidirectional"))
    )
    (net (code "104") (name "unconnected-(CON1-NC-Pad39)") (class "Default")
      (node (ref "CON1") (pin "39") (pinfunction "NC_39") (pintype "bidirectional"))
    )
    (net (code "105") (name "unconnected-(CON1-NC-Pad40)") (class "Default")
      (node (ref "CON1") (pin "40") (pinfunction "NC_40") (pintype "bidirectional"))
    )
    (net (code "106") (name "unconnected-(IC1A-BOOT0-Pad197)") (class "Default")
      (node (ref "IC1") (pin "197") (pinfunction "BOOT0_197") (pintype "input"))
    )
    (net (code "107") (name "unconnected-(IC1A-PA0-Pad43)") (class "Default")
      (node (ref "IC1") (pin "43") (pinfunction "PA0_43") (pintype "bidirectional"))
    )
    (net (code "108") (name "unconnected-(IC1A-PA5-Pad54)") (class "Default")
      (node (ref "IC1") (pin "54") (pinfunction "PA5_54") (pintype "bidirectional"))
    )
    (net (code "109") (name "unconnected-(IC1A-PA9-Pad143)") (class "Default")
      (node (ref "IC1") (pin "143") (pinfunction "PA9_143") (pintype "bidirectional"))
    )
    (net (code "110") (name "unconnected-(IC1A-PA10-Pad144)") (class "Default")
      (node (ref "IC1") (pin "144") (pinfunction "PA10_144") (pintype "bidirectional"))
    )
    (net (code "111") (name "unconnected-(IC1A-PB0-Pad61)") (class "Default")
      (node (ref "IC1") (pin "61") (pinfunction "PB0_61") (pintype "bidirectional"))
    )
    (net (code "112") (name "unconnected-(IC1A-PB1-Pad62)") (class "Default")
      (node (ref "IC1") (pin "62") (pinfunction "PB1_62") (pintype "bidirectional"))
    )
    (net (code "113") (name "unconnected-(IC1A-PB2-Pad63)") (class "Default")
      (node (ref "IC1") (pin "63") (pinfunction "PB2_63") (pintype "bidirectional"))
    )
    (net (code "114") (name "unconnected-(IC1A-PB5-Pad194)") (class "Default")
      (node (ref "IC1") (pin "194") (pinfunction "PB5_194") (pintype "bidirectional"))
    )
    (net (code "115") (name "unconnected-(IC1A-PB6-Pad195)") (class "Default")
      (node (ref "IC1") (pin "195") (pinfunction "PB6_195") (pintype "bidirectional"))
    )
    (net (code "116") (name "unconnected-(IC1A-PB7-Pad196)") (class "Default")
      (node (ref "IC1") (pin "196") (pinfunction "PB7_196") (pintype "bidirectional"))
    )
    (net (code "117") (name "unconnected-(IC1A-PB10-Pad90)") (class "Default")
      (node (ref "IC1") (pin "90") (pinfunction "PB10_90") (pintype "bidirectional"))
    )
    (net (code "118") (name "unconnected-(IC1A-PB11-Pad91)") (class "Default")
      (node (ref "IC1") (pin "91") (pinfunction "PB11_91") (pintype "bidirectional"))
    )
    (net (code "119") (name "unconnected-(IC1A-PB12-Pad104)") (class "Default")
      (node (ref "IC1") (pin "104") (pinfunction "PB12_104") (pintype "bidirectional"))
    )
    (net (code "120") (name "unconnected-(IC1A-PB13-Pad105)") (class "Default")
      (node (ref "IC1") (pin "105") (pinfunction "PB13_105") (pintype "bidirectional"))
    )
    (net (code "121") (name "unconnected-(IC1A-PC0-Pad35)") (class "Default")
      (node (ref "IC1") (pin "35") (pinfunction "PC0_35") (pintype "bidirectional"))
    )
    (net (code "122") (name "unconnected-(IC1A-PC1-Pad36)") (class "Default")
      (node (ref "IC1") (pin "36") (pinfunction "PC1_36") (pintype "bidirectional"))
    )
    (net (code "123") (name "unconnected-(IC1A-PC4-Pad57)") (class "Default")
      (node (ref "IC1") (pin "57") (pinfunction "PC4_57") (pintype "bidirectional"))
    )
    (net (code "124") (name "unconnected-(IC1A-PC5-Pad58)") (class "Default")
      (node (ref "IC1") (pin "58") (pinfunction "PC5_58") (pintype "bidirectional"))
    )
    (net (code "125") (name "unconnected-(IC1A-PC13-Pad8)") (class "Default")
      (node (ref "IC1") (pin "8") (pinfunction "PC13_8") (pintype "bidirectional"))
    )
    (net (code "126") (name "unconnected-(IC1A-PC14-Pad9)") (class "Default")
      (node (ref "IC1") (pin "9") (pinfunction "PC14_9") (pintype "bidirectional"))
    )
    (net (code "127") (name "unconnected-(IC1A-PC15-Pad10)") (class "Default")
      (node (ref "IC1") (pin "10") (pinfunction "PC15_10") (pintype "bidirectional"))
    )
    (net (code "128") (name "unconnected-(IC1A-PD0-Pad164)") (class "Default")
      (node (ref "IC1") (pin "164") (pinfunction "PD0_164") (pintype "bidirectional"))
    )
    (net (code "129") (name "unconnected-(IC1A-PD1-Pad165)") (class "Default")
      (node (ref "IC1") (pin "165") (pinfunction "PD1_165") (pintype "bidirectional"))
    )
    (net (code "130") (name "unconnected-(IC1A-PD4-Pad168)") (class "Default")
      (node (ref "IC1") (pin "168") (pinfunction "PD4_168") (pintype "bidirectional"))
    )
    (net (code "131") (name "unconnected-(IC1A-PD5-Pad169)") (class "Default")
      (node (ref "IC1") (pin "169") (pinfunction "PD5_169") (pintype "bidirectional"))
    )
    (net (code "132") (name "unconnected-(IC1A-PD7-Pad173)") (class "Default")
      (node (ref "IC1") (pin "173") (pinfunction "PD7_173") (pintype "bidirectional"))
    )
    (net (code "133") (name "unconnected-(IC1A-PDR_ON-Pad203)") (class "Default")
      (node (ref "IC1") (pin "203") (pinfunction "PDR_ON_203") (pintype "input"))
    )
    (net (code "134") (name "unconnected-(IC1A-PE0-Pad200)") (class "Default")
      (node (ref "IC1") (pin "200") (pinfunction "PE0_200") (pintype "bidirectional"))
    )
    (net (code "135") (name "unconnected-(IC1A-PE1-Pad201)") (class "Default")
      (node (ref "IC1") (pin "201") (pinfunction "PE1_201") (pintype "bidirectional"))
    )
    (net (code "136") (name "unconnected-(IC1A-PE2-Pad1)") (class "Default")
      (node (ref "IC1") (pin "1") (pinfunction "PE2_1") (pintype "bidirectional"))
    )
    (net (code "137") (name "unconnected-(IC1A-PE3-Pad2)") (class "Default")
      (node (ref "IC1") (pin "2") (pinfunction "PE3_2") (pintype "bidirectional"))
    )
    (net (code "138") (name "unconnected-(IC1A-PE7-Pad79)") (class "Default")
      (node (ref "IC1") (pin "79") (pinfunction "PE7_79") (pintype "bidirectional"))
    )
    (net (code "139") (name "unconnected-(IC1A-PE8-Pad80)") (class "Default")
      (node (ref "IC1") (pin "80") (pinfunction "PE8_80") (pintype "bidirectional"))
    )
    (net (code "140") (name "unconnected-(IC1A-PE9-Pad81)") (class "Default")
      (node (ref "IC1") (pin "81") (pinfunction "PE9_81") (pintype "bidirectional"))
    )
    (net (code "141") (name "unconnected-(IC1A-PE10-Pad84)") (class "Default")
      (node (ref "IC1") (pin "84") (pinfunction "PE10_84") (pintype "bidirectional"))
    )
    (net (code "142") (name "unconnected-(IC1A-PF3-Pad22)") (class "Default")
      (node (ref "IC1") (pin "22") (pinfunction "PF3_22") (pintype "bidirectional"))
    )
    (net (code "143") (name "unconnected-(IC1A-PF4-Pad23)") (class "Default")
      (node (ref "IC1") (pin "23") (pinfunction "PF4_23") (pintype "bidirectional"))
    )
    (net (code "144") (name "unconnected-(IC1A-PF5-Pad24)") (class "Default")
      (node (ref "IC1") (pin "24") (pinfunction "PF5_24") (pintype "bidirectional"))
    )
    (net (code "145") (name "unconnected-(IC1A-PF6-Pad27)") (class "Default")
      (node (ref "IC1") (pin "27") (pinfunction "PF6_27") (pintype "bidirectional"))
    )
    (net (code "146") (name "unconnected-(IC1A-PF7-Pad28)") (class "Default")
      (node (ref "IC1") (pin "28") (pinfunction "PF7_28") (pintype "bidirectional"))
    )
    (net (code "147") (name "unconnected-(IC1A-PF8-Pad29)") (class "Default")
      (node (ref "IC1") (pin "29") (pinfunction "PF8_29") (pintype "bidirectional"))
    )
    (net (code "148") (name "unconnected-(IC1A-PF9-Pad30)") (class "Default")
      (node (ref "IC1") (pin "30") (pinfunction "PF9_30") (pintype "bidirectional"))
    )
    (net (code "149") (name "unconnected-(IC1A-PF10-Pad31)") (class "Default")
      (node (ref "IC1") (pin "31") (pinfunction "PF10_31") (pintype "bidirectional"))
    )
    (net (code "150") (name "unconnected-(IC1A-PF11-Pad70)") (class "Default")
      (node (ref "IC1") (pin "70") (pinfunction "PF11_70") (pintype "bidirectional"))
    )
    (net (code "151") (name "unconnected-(IC1A-PF12-Pad71)") (class "Default")
      (node (ref "IC1") (pin "71") (pinfunction "PF12_71") (pintype "bidirectional"))
    )
    (net (code "152") (name "unconnected-(IC1A-PF13-Pad74)") (class "Default")
      (node (ref "IC1") (pin "74") (pinfunction "PF13_74") (pintype "bidirectional"))
    )
    (net (code "153") (name "unconnected-(IC1A-PF14-Pad75)") (class "Default")
      (node (ref "IC1") (pin "75") (pinfunction "PF14_75") (pintype "bidirectional"))
    )
    (net (code "154") (name "unconnected-(IC1A-PF15-Pad76)") (class "Default")
      (node (ref "IC1") (pin "76") (pinfunction "PF15_76") (pintype "bidirectional"))
    )
    (net (code "155") (name "unconnected-(IC1A-PG0-Pad77)") (class "Default")
      (node (ref "IC1") (pin "77") (pinfunction "PG0_77") (pintype "bidirectional"))
    )
    (net (code "156") (name "unconnected-(IC1A-PG1-Pad78)") (class "Default")
      (node (ref "IC1") (pin "78") (pinfunction "PG1_78") (pintype "bidirectional"))
    )
    (net (code "157") (name "unconnected-(IC1A-PG2-Pad129)") (class "Default")
      (node (ref "IC1") (pin "129") (pinfunction "PG2_129") (pintype "bidirectional"))
    )
    (net (code "158") (name "unconnected-(IC1A-PG3-Pad130)") (class "Default")
      (node (ref "IC1") (pin "130") (pinfunction "PG3_130") (pintype "bidirectional"))
    )
    (net (code "159") (name "unconnected-(IC1A-PG4-Pad131)") (class "Default")
      (node (ref "IC1") (pin "131") (pinfunction "PG4_131") (pintype "bidirectional"))
    )
    (net (code "160") (name "unconnected-(IC1A-PG5-Pad132)") (class "Default")
      (node (ref "IC1") (pin "132") (pinfunction "PG5_132") (pintype "bidirectional"))
    )
    (net (code "161") (name "unconnected-(IC1A-PG6-Pad133)") (class "Default")
      (node (ref "IC1") (pin "133") (pinfunction "PG6_133") (pintype "bidirectional"))
    )
    (net (code "162") (name "unconnected-(IC1A-PG10-Pad179)") (class "Default")
      (node (ref "IC1") (pin "179") (pinfunction "PG10_179") (pintype "bidirectional"))
    )
    (net (code "163") (name "unconnected-(IC1A-PG11-Pad180)") (class "Default")
      (node (ref "IC1") (pin "180") (pinfunction "PG11_180") (pintype "bidirectional"))
    )
    (net (code "164") (name "unconnected-(IC1A-PG15-Pad191)") (class "Default")
      (node (ref "IC1") (pin "191") (pinfunction "PG15_191") (pintype "bidirectional"))
    )
    (net (code "165") (name "unconnected-(IC1A-PH4-Pad48)") (class "Default")
      (node (ref "IC1") (pin "48") (pinfunction "PH4_48") (pintype "bidirectional"))
    )
    (net (code "166") (name "unconnected-(IC1A-PH5-Pad49)") (class "Default")
      (node (ref "IC1") (pin "49") (pinfunction "PH5_49") (pintype "bidirectional"))
    )
    (net (code "167") (name "unconnected-(IC1A-PH6-Pad96)") (class "Default")
      (node (ref "IC1") (pin "96") (pinfunction "PH6_96") (pintype "bidirectional"))
    )
    (net (code "168") (name "unconnected-(IC1A-PH7-Pad97)") (class "Default")
      (node (ref "IC1") (pin "97") (pinfunction "PH7_97") (pintype "bidirectional"))
    )
    (net (code "169") (name "unconnected-(IC1A-PH10-Pad100)") (class "Default")
      (node (ref "IC1") (pin "100") (pinfunction "PH10_100") (pintype "bidirectional"))
    )
    (net (code "170") (name "unconnected-(IC1A-PH11-Pad101)") (class "Default")
      (node (ref "IC1") (pin "101") (pinfunction "PH11_101") (pintype "bidirectional"))
    )
    (net (code "171") (name "unconnected-(IC1A-PH12-Pad102)") (class "Default")
      (node (ref "IC1") (pin "102") (pinfunction "PH12_102") (pintype "bidirectional"))
    )
    (net (code "172") (name "unconnected-(IC1A-PH13-Pad151)") (class "Default")
      (node (ref "IC1") (pin "151") (pinfunction "PH13_151") (pintype "bidirectional"))
    )
    (net (code "173") (name "unconnected-(IC1A-PH14-Pad152)") (class "Default")
      (node (ref "IC1") (pin "152") (pinfunction "PH14_152") (pintype "bidirectional"))
    )
    (net (code "174") (name "unconnected-(IC1A-PI2-Pad156)") (class "Default")
      (node (ref "IC1") (pin "156") (pinfunction "PI2_156") (pintype "bidirectional"))
    )
    (net (code "175") (name "unconnected-(IC1A-PI3-Pad157)") (class "Default")
      (node (ref "IC1") (pin "157") (pinfunction "PI3_157") (pintype "bidirectional"))
    )
    (net (code "176") (name "unconnected-(IC1A-PI4-Pad205)") (class "Default")
      (node (ref "IC1") (pin "205") (pinfunction "PI4_205") (pintype "bidirectional"))
    )
    (net (code "177") (name "unconnected-(IC1A-PI8-Pad7)") (class "Default")
      (node (ref "IC1") (pin "7") (pinfunction "PI8_7") (pintype "bidirectional"))
    )
    (net (code "178") (name "unconnected-(IC1A-PI11-Pad13)") (class "Default")
      (node (ref "IC1") (pin "13") (pinfunction "PI11_13") (pintype "bidirectional"))
    )
    (net (code "179") (name "unconnected-(IC1A-PI12-Pad19)") (class "Default")
      (node (ref "IC1") (pin "19") (pinfunction "PI12_19") (pintype "bidirectional"))
    )
    (net (code "180") (name "unconnected-(IC1A-PI13-Pad20)") (class "Default")
      (node (ref "IC1") (pin "20") (pinfunction "PI13_20") (pintype "bidirectional"))
    )
    (net (code "181") (name "unconnected-(IC1A-PI14-Pad21)") (class "Default")
      (node (ref "IC1") (pin "21") (pinfunction "PI14_21") (pintype "bidirectional"))
    )
    (net (code "182") (name "unconnected-(IC1A-PI15-Pad64)") (class "Default")
      (node (ref "IC1") (pin "64") (pinfunction "PI15_64") (pintype "bidirectional"))
    )
    (net (code "183") (name "unconnected-(IC1A-PK2-Pad128)") (class "Default")
      (node (ref "IC1") (pin "128") (pinfunction "PK2_128") (pintype "bidirectional"))
    )
    (net (code "184") (name "unconnected-(IC1A-PK3-Pad186)") (class "Default")
      (node (ref "IC1") (pin "186") (pinfunction "PK3_186") (pintype "bidirectional"))
    )
    (net (code "185") (name "unconnected-(IC1A-PK4-Pad187)") (class "Default")
      (node (ref "IC1") (pin "187") (pinfunction "PK4_187") (pintype "bidirectional"))
    )
    (net (code "186") (name "unconnected-(IC1A-PK5-Pad188)") (class "Default")
      (node (ref "IC1") (pin "188") (pinfunction "PK5_188") (pintype "bidirectional"))
    )
    (net (code "187") (name "unconnected-(IC1A-PK6-Pad189)") (class "Default")
      (node (ref "IC1") (pin "189") (pinfunction "PK6_189") (pintype "bidirectional"))
    )
    (net (code "188") (name "unconnected-(IC1A-PK7-Pad190)") (class "Default")
      (node (ref "IC1") (pin "190") (pinfunction "PK7_190") (pintype "bidirectional"))
    )
    (net (code "189") (name "unconnected-(JP1-Pad6)") (class "Default")
      (node (ref "JP1") (pin "6") (pinfunction "6_6") (pintype "passive"))
    )
    (net (code "190") (name "unconnected-(JP1-Pad7)") (class "Default")
      (node (ref "JP1") (pin "7") (pinfunction "7_7") (pintype "passive"))
    )
    (net (code "191") (name "unconnected-(JP1-Pad8)") (class "Default")
      (node (ref "JP1") (pin "8") (pinfunction "8_8") (pintype "passive"))
    )
    (net (code "192") (name "unconnected-(U$1-0P4V-Pad10)") (class "Default")
      (node (ref "U$1") (pin "10") (pinfunction "0P4V_10") (pintype "bidirectional"))
    )
    (net (code "193") (name "unconnected-(U$1-0P8V-Pad9)") (class "Default")
      (node (ref "U$1") (pin "9") (pinfunction "0P8V_9") (pintype "bidirectional"))
    )
    (net (code "194") (name "unconnected-(U$1-3P2V-Pad6)") (class "Default")
      (node (ref "U$1") (pin "6") (pinfunction "3P2V_6") (pintype "bidirectional"))
    )
    (net (code "195") (name "unconnected-(U$1-6P4V1-Pad5)") (class "Default")
      (node (ref "U$1") (pin "5") (pinfunction "6P4V1_5") (pintype "bidirectional"))
    )
    (net (code "196") (name "unconnected-(U$1-6P4V2-Pad4)") (class "Default")
      (node (ref "U$1") (pin "4") (pinfunction "6P4V2_4") (pintype "bidirectional"))
    )
    (net (code "197") (name "unconnected-(U$1-NC-Pad2)") (class "Default")
      (node (ref "U$1") (pin "2") (pinfunction "NC_2") (pintype "bidirectional"))
    )
    (net (code "198") (name "unconnected-(U$1-NC-Pad17)") (class "Default")
      (node (ref "U$1") (pin "17") (pinfunction "NC_17") (pintype "bidirectional"))
    )
    (net (code "199") (name "unconnected-(U$1-NC-Pad18)") (class "Default")
      (node (ref "U$1") (pin "18") (pinfunction "NC_18") (pintype "bidirectional"))
    )
    (net (code "200") (name "unconnected-(U$1-NC-Pad19)") (class "Default")
      (node (ref "U$1") (pin "19") (pinfunction "NC_19") (pintype "bidirectional"))
    )
    (net (code "201") (name "unconnected-(U$1-NR-Pad14)") (class "Default")
      (node (ref "U$1") (pin "14") (pinfunction "NR_14") (pintype "bidirectional"))
    )
    (net (code "202") (name "unconnected-(U$1-SENSE{slash}FB-Pad3)") (class "Default")
      (node (ref "U$1") (pin "3") (pinfunction "SENSE/FB_3") (pintype "bidirectional"))
    )
    (net (code "203") (name "unconnected-(U$2-0P1V-Pad12)") (class "Default")
      (node (ref "U$2") (pin "12") (pinfunction "0P1V_12") (pintype "bidirectional"))
    )
    (net (code "204") (name "unconnected-(U$2-0P2V-Pad11)") (class "Default")
      (node (ref "U$2") (pin "11") (pinfunction "0P2V_11") (pintype "bidirectional"))
    )
    (net (code "205") (name "unconnected-(U$2-0P8V-Pad9)") (class "Default")
      (node (ref "U$2") (pin "9") (pinfunction "0P8V_9") (pintype "bidirectional"))
    )
    (net (code "206") (name "unconnected-(U$2-1P6V-Pad8)") (class "Default")
      (node (ref "U$2") (pin "8") (pinfunction "1P6V_8") (pintype "bidirectional"))
    )
    (net (code "207") (name "unconnected-(U$2-6P4V1-Pad5)") (class "Default")
      (node (ref "U$2") (pin "5") (pinfunction "6P4V1_5") (pintype "bidirectional"))
    )
    (net (code "208") (name "unconnected-(U$2-6P4V2-Pad4)") (class "Default")
      (node (ref "U$2") (pin "4") (pinfunction "6P4V2_4") (pintype "bidirectional"))
    )
    (net (code "209") (name "unconnected-(U$2-NC-Pad2)") (class "Default")
      (node (ref "U$2") (pin "2") (pinfunction "NC_2") (pintype "bidirectional"))
    )
    (net (code "210") (name "unconnected-(U$2-NC-Pad17)") (class "Default")
      (node (ref "U$2") (pin "17") (pinfunction "NC_17") (pintype "bidirectional"))
    )
    (net (code "211") (name "unconnected-(U$2-NC-Pad18)") (class "Default")
      (node (ref "U$2") (pin "18") (pinfunction "NC_18") (pintype "bidirectional"))
    )
    (net (code "212") (name "unconnected-(U$2-NC-Pad19)") (class "Default")
      (node (ref "U$2") (pin "19") (pinfunction "NC_19") (pintype "bidirectional"))
    )
    (net (code "213") (name "unconnected-(U$2-NR-Pad14)") (class "Default")
      (node (ref "U$2") (pin "14") (pinfunction "NR_14") (pintype "bidirectional"))
    )
    (net (code "214") (name "unconnected-(U$2-SENSE{slash}FB-Pad3)") (class "Default")
      (node (ref "U$2") (pin "3") (pinfunction "SENSE/FB_3") (pintype "bidirectional"))
    )
  )
)
